# Balancer.net
KiCad netlist of a schematic drawn in Altium Designer
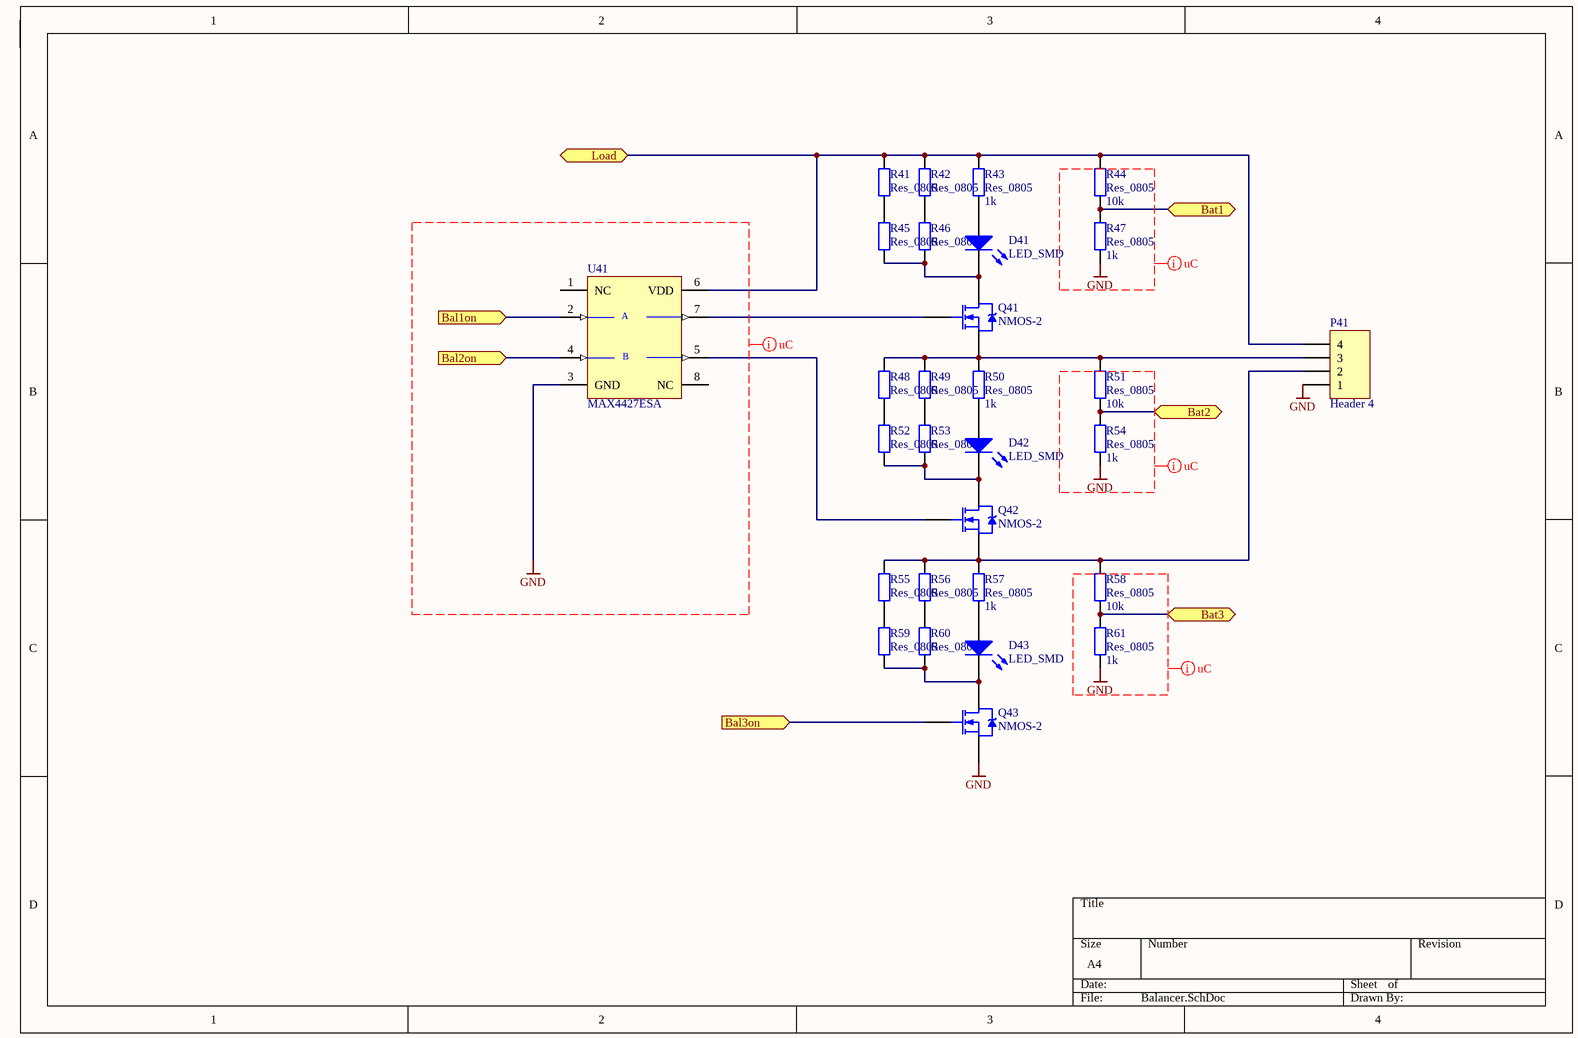
[diagram p0: Balancer.SchDoc]

(export (version "E")
  (design (tool "Eeschema 10.0.6"))
  (components
    (comp (ref "D41") (value "LED_SMD") (footprint "LED_SMD") (libsource (lib "Diodes$") (part "DIODE_48")))
    (comp (ref "D42") (value "LED_SMD") (footprint "LED_SMD") (libsource (lib "Diodes$") (part "DIODE_48")))
    (comp (ref "D43") (value "LED_SMD") (footprint "LED_SMD") (libsource (lib "Diodes$") (part "DIODE_48")))
    (comp (ref "P41") (value "Header 4") (footprint "HDR1X4") (libsource (lib "Connectors$") (part "Con_33")))
    (comp (ref "Q41")
      (value "NMOS-2")
      (footprint "SOT23_N")
      (description "N-Channel Power MOSFET")
      (fields (field (name "PUBLISHER") "Altium Limited"))
      (libsource (lib "Miscellaneous Devices") (part "NMOS-2"))
    )
    (comp (ref "Q42")
      (value "NMOS-2")
      (footprint "SOT23_N")
      (description "N-Channel Power MOSFET")
      (fields (field (name "PUBLISHER") "Altium Limited"))
      (libsource (lib "Miscellaneous Devices") (part "NMOS-2"))
    )
    (comp (ref "Q43")
      (value "NMOS-2")
      (footprint "SOT23_N")
      (description "N-Channel Power MOSFET")
      (fields (field (name "PUBLISHER") "Altium Limited"))
      (libsource (lib "Miscellaneous Devices") (part "NMOS-2"))
    )
    (comp (ref "R41") (value "Res_0805") (footprint "_0805") (libsource (lib "Resistors$") (part "Res_6")))
    (comp (ref "R42") (value "Res_0805") (footprint "_0805") (libsource (lib "Resistors$") (part "Res_6")))
    (comp (ref "R43")
      (value "Res_0805")
      (footprint "_0805")
      (fields (field (name "ALTIUM_VALUE") "1k"))
      (libsource (lib "Resistors$") (part "Res_6"))
    )
    (comp (ref "R44")
      (value "Res_0805")
      (footprint "_0805")
      (fields (field (name "ALTIUM_VALUE") "10k"))
      (libsource (lib "Resistors$") (part "Res_6"))
    )
    (comp (ref "R45") (value "Res_0805") (footprint "_0805") (libsource (lib "Resistors$") (part "Res_6")))
    (comp (ref "R46") (value "Res_0805") (footprint "_0805") (libsource (lib "Resistors$") (part "Res_6")))
    (comp (ref "R47")
      (value "Res_0805")
      (footprint "_0805")
      (fields (field (name "ALTIUM_VALUE") "1k"))
      (libsource (lib "Resistors$") (part "Res_6"))
    )
    (comp (ref "R48") (value "Res_0805") (footprint "_0805") (libsource (lib "Resistors$") (part "Res_6")))
    (comp (ref "R49") (value "Res_0805") (footprint "_0805") (libsource (lib "Resistors$") (part "Res_6")))
    (comp (ref "R50")
      (value "Res_0805")
      (footprint "_0805")
      (fields (field (name "ALTIUM_VALUE") "1k"))
      (libsource (lib "Resistors$") (part "Res_6"))
    )
    (comp (ref "R51")
      (value "Res_0805")
      (footprint "_0805")
      (fields (field (name "ALTIUM_VALUE") "10k"))
      (libsource (lib "Resistors$") (part "Res_6"))
    )
    (comp (ref "R52") (value "Res_0805") (footprint "_0805") (libsource (lib "Resistors$") (part "Res_6")))
    (comp (ref "R53") (value "Res_0805") (footprint "_0805") (libsource (lib "Resistors$") (part "Res_6")))
    (comp (ref "R54")
      (value "Res_0805")
      (footprint "_0805")
      (fields (field (name "ALTIUM_VALUE") "1k"))
      (libsource (lib "Resistors$") (part "Res_6"))
    )
    (comp (ref "R55") (value "Res_0805") (footprint "_0805") (libsource (lib "Resistors$") (part "Res_6")))
    (comp (ref "R56") (value "Res_0805") (footprint "_0805") (libsource (lib "Resistors$") (part "Res_6")))
    (comp (ref "R57")
      (value "Res_0805")
      (footprint "_0805")
      (fields (field (name "ALTIUM_VALUE") "1k"))
      (libsource (lib "Resistors$") (part "Res_6"))
    )
    (comp (ref "R58")
      (value "Res_0805")
      (footprint "_0805")
      (fields (field (name "ALTIUM_VALUE") "10k"))
      (libsource (lib "Resistors$") (part "Res_6"))
    )
    (comp (ref "R59") (value "Res_0805") (footprint "_0805") (libsource (lib "Resistors$") (part "Res_6")))
    (comp (ref "R60") (value "Res_0805") (footprint "_0805") (libsource (lib "Resistors$") (part "Res_6")))
    (comp (ref "R61")
      (value "Res_0805")
      (footprint "_0805")
      (fields (field (name "ALTIUM_VALUE") "1k"))
      (libsource (lib "Resistors$") (part "Res_6"))
    )
    (comp (ref "U41")
      (value "MAX4427ESA")
      (footprint "NSO8_N")
      (description "Dual High-Speed 1.5A MOSFET Driver")
      (fields (field (name "PUBLISHER") "Altium Limited"))
      (libsource (lib "Maxim Interface MOSFET Driver") (part "MAX4427ESA"))
    )
  )
  (nets
    (net (code "1") (name "/Bal1on") (class "Default")
      (node (ref "U41") (pin "2") (pinfunction "INA_2") (pintype "input"))
    )
    (net (code "2") (name "/Bal2on") (class "Default")
      (node (ref "U41") (pin "4") (pinfunction "INB_4") (pintype "input"))
    )
    (net (code "3") (name "/Bal3on") (class "Default")
      (node (ref "Q43") (pin "1") (pinfunction "G_1") (pintype "passive"))
    )
    (net (code "4") (name "/Bat1") (class "Default")
      (node (ref "R44") (pin "1") (pinfunction "1_1") (pintype "passive"))
      (node (ref "R47") (pin "2") (pinfunction "2_2") (pintype "passive"))
    )
    (net (code "5") (name "/Bat2") (class "Default")
      (node (ref "R51") (pin "1") (pinfunction "1_1") (pintype "passive"))
      (node (ref "R54") (pin "2") (pinfunction "2_2") (pintype "passive"))
    )
    (net (code "6") (name "/Bat3") (class "Default")
      (node (ref "R58") (pin "1") (pinfunction "1_1") (pintype "passive"))
      (node (ref "R61") (pin "2") (pinfunction "2_2") (pintype "passive"))
    )
    (net (code "7") (name "/Load") (class "Default")
      (node (ref "P41") (pin "4") (pinfunction "4_4") (pintype "passive"))
      (node (ref "R41") (pin "2") (pinfunction "2_2") (pintype "passive"))
      (node (ref "R42") (pin "2") (pinfunction "2_2") (pintype "passive"))
      (node (ref "R43") (pin "2") (pinfunction "2_2") (pintype "passive"))
      (node (ref "R44") (pin "2") (pinfunction "2_2") (pintype "passive"))
      (node (ref "U41") (pin "6") (pinfunction "VDD_6") (pintype "power_in"))
    )
    (net (code "8") (name "GND") (class "Default")
      (node (ref "P41") (pin "1") (pinfunction "1_1") (pintype "passive"))
      (node (ref "Q43") (pin "2") (pinfunction "S_2") (pintype "passive"))
      (node (ref "R47") (pin "1") (pinfunction "1_1") (pintype "passive"))
      (node (ref "R54") (pin "1") (pinfunction "1_1") (pintype "passive"))
      (node (ref "R61") (pin "1") (pinfunction "1_1") (pintype "passive"))
      (node (ref "U41") (pin "3") (pinfunction "GND_3") (pintype "power_in"))
    )
    (net (code "9") (name "Net-(D41-Pad1)") (class "Default")
      (node (ref "D41") (pin "1") (pinfunction "1_1") (pintype "passive"))
      (node (ref "R43") (pin "1") (pinfunction "1_1") (pintype "passive"))
    )
    (net (code "10") (name "Net-(D42-Pad1)") (class "Default")
      (node (ref "D42") (pin "1") (pinfunction "1_1") (pintype "passive"))
      (node (ref "R50") (pin "1") (pinfunction "1_1") (pintype "passive"))
    )
    (net (code "11") (name "Net-(D43-Pad1)") (class "Default")
      (node (ref "D43") (pin "1") (pinfunction "1_1") (pintype "passive"))
      (node (ref "R57") (pin "1") (pinfunction "1_1") (pintype "passive"))
    )
    (net (code "12") (name "Net-(Q41-D)") (class "Default")
      (node (ref "D41") (pin "2") (pinfunction "2_2") (pintype "passive"))
      (node (ref "Q41") (pin "3") (pinfunction "D_3") (pintype "passive"))
      (node (ref "R45") (pin "1") (pinfunction "1_1") (pintype "passive"))
      (node (ref "R46") (pin "1") (pinfunction "1_1") (pintype "passive"))
    )
    (net (code "13") (name "Net-(Q41-G)") (class "Default")
      (node (ref "Q41") (pin "1") (pinfunction "G_1") (pintype "passive"))
      (node (ref "U41") (pin "7") (pinfunction "OUTA_7") (pintype "output"))
    )
    (net (code "14") (name "Net-(Q41-S)") (class "Default")
      (node (ref "P41") (pin "3") (pinfunction "3_3") (pintype "passive"))
      (node (ref "Q41") (pin "2") (pinfunction "S_2") (pintype "passive"))
      (node (ref "R48") (pin "2") (pinfunction "2_2") (pintype "passive"))
      (node (ref "R49") (pin "2") (pinfunction "2_2") (pintype "passive"))
      (node (ref "R50") (pin "2") (pinfunction "2_2") (pintype "passive"))
      (node (ref "R51") (pin "2") (pinfunction "2_2") (pintype "passive"))
    )
    (net (code "15") (name "Net-(Q42-D)") (class "Default")
      (node (ref "D42") (pin "2") (pinfunction "2_2") (pintype "passive"))
      (node (ref "Q42") (pin "3") (pinfunction "D_3") (pintype "passive"))
      (node (ref "R52") (pin "1") (pinfunction "1_1") (pintype "passive"))
      (node (ref "R53") (pin "1") (pinfunction "1_1") (pintype "passive"))
    )
    (net (code "16") (name "Net-(Q42-G)") (class "Default")
      (node (ref "Q42") (pin "1") (pinfunction "G_1") (pintype "passive"))
      (node (ref "U41") (pin "5") (pinfunction "OUTB_5") (pintype "output"))
    )
    (net (code "17") (name "Net-(Q42-S)") (class "Default")
      (node (ref "P41") (pin "2") (pinfunction "2_2") (pintype "passive"))
      (node (ref "Q42") (pin "2") (pinfunction "S_2") (pintype "passive"))
      (node (ref "R55") (pin "2") (pinfunction "2_2") (pintype "passive"))
      (node (ref "R56") (pin "2") (pinfunction "2_2") (pintype "passive"))
      (node (ref "R57") (pin "2") (pinfunction "2_2") (pintype "passive"))
      (node (ref "R58") (pin "2") (pinfunction "2_2") (pintype "passive"))
    )
    (net (code "18") (name "Net-(Q43-D)") (class "Default")
      (node (ref "D43") (pin "2") (pinfunction "2_2") (pintype "passive"))
      (node (ref "Q43") (pin "3") (pinfunction "D_3") (pintype "passive"))
      (node (ref "R59") (pin "1") (pinfunction "1_1") (pintype "passive"))
      (node (ref "R60") (pin "1") (pinfunction "1_1") (pintype "passive"))
    )
    (net (code "19") (name "Net-(R41-Pad1)") (class "Default")
      (node (ref "R41") (pin "1") (pinfunction "1_1") (pintype "passive"))
      (node (ref "R45") (pin "2") (pinfunction "2_2") (pintype "passive"))
    )
    (net (code "20") (name "Net-(R42-Pad1)") (class "Default")
      (node (ref "R42") (pin "1") (pinfunction "1_1") (pintype "passive"))
      (node (ref "R46") (pin "2") (pinfunction "2_2") (pintype "passive"))
    )
    (net (code "21") (name "Net-(R48-Pad1)") (class "Default")
      (node (ref "R48") (pin "1") (pinfunction "1_1") (pintype "passive"))
      (node (ref "R52") (pin "2") (pinfunction "2_2") (pintype "passive"))
    )
    (net (code "22") (name "Net-(R49-Pad1)") (class "Default")
      (node (ref "R49") (pin "1") (pinfunction "1_1") (pintype "passive"))
      (node (ref "R53") (pin "2") (pinfunction "2_2") (pintype "passive"))
    )
    (net (code "23") (name "Net-(R55-Pad1)") (class "Default")
      (node (ref "R55") (pin "1") (pinfunction "1_1") (pintype "passive"))
      (node (ref "R59") (pin "2") (pinfunction "2_2") (pintype "passive"))
    )
    (net (code "24") (name "Net-(R56-Pad1)") (class "Default")
      (node (ref "R56") (pin "1") (pinfunction "1_1") (pintype "passive"))
      (node (ref "R60") (pin "2") (pinfunction "2_2") (pintype "passive"))
    )
    (net (code "25") (name "unconnected-(U41-NC-Pad1)") (class "Default")
      (node (ref "U41") (pin "1") (pinfunction "NC_1") (pintype "passive"))
    )
    (net (code "26") (name "unconnected-(U41-NC-Pad8)") (class "Default")
      (node (ref "U41") (pin "8") (pinfunction "NC_8") (pintype "passive"))
    )
  )
)
